# Schematic.net
KiCad netlist of a schematic drawn in Altium Designer
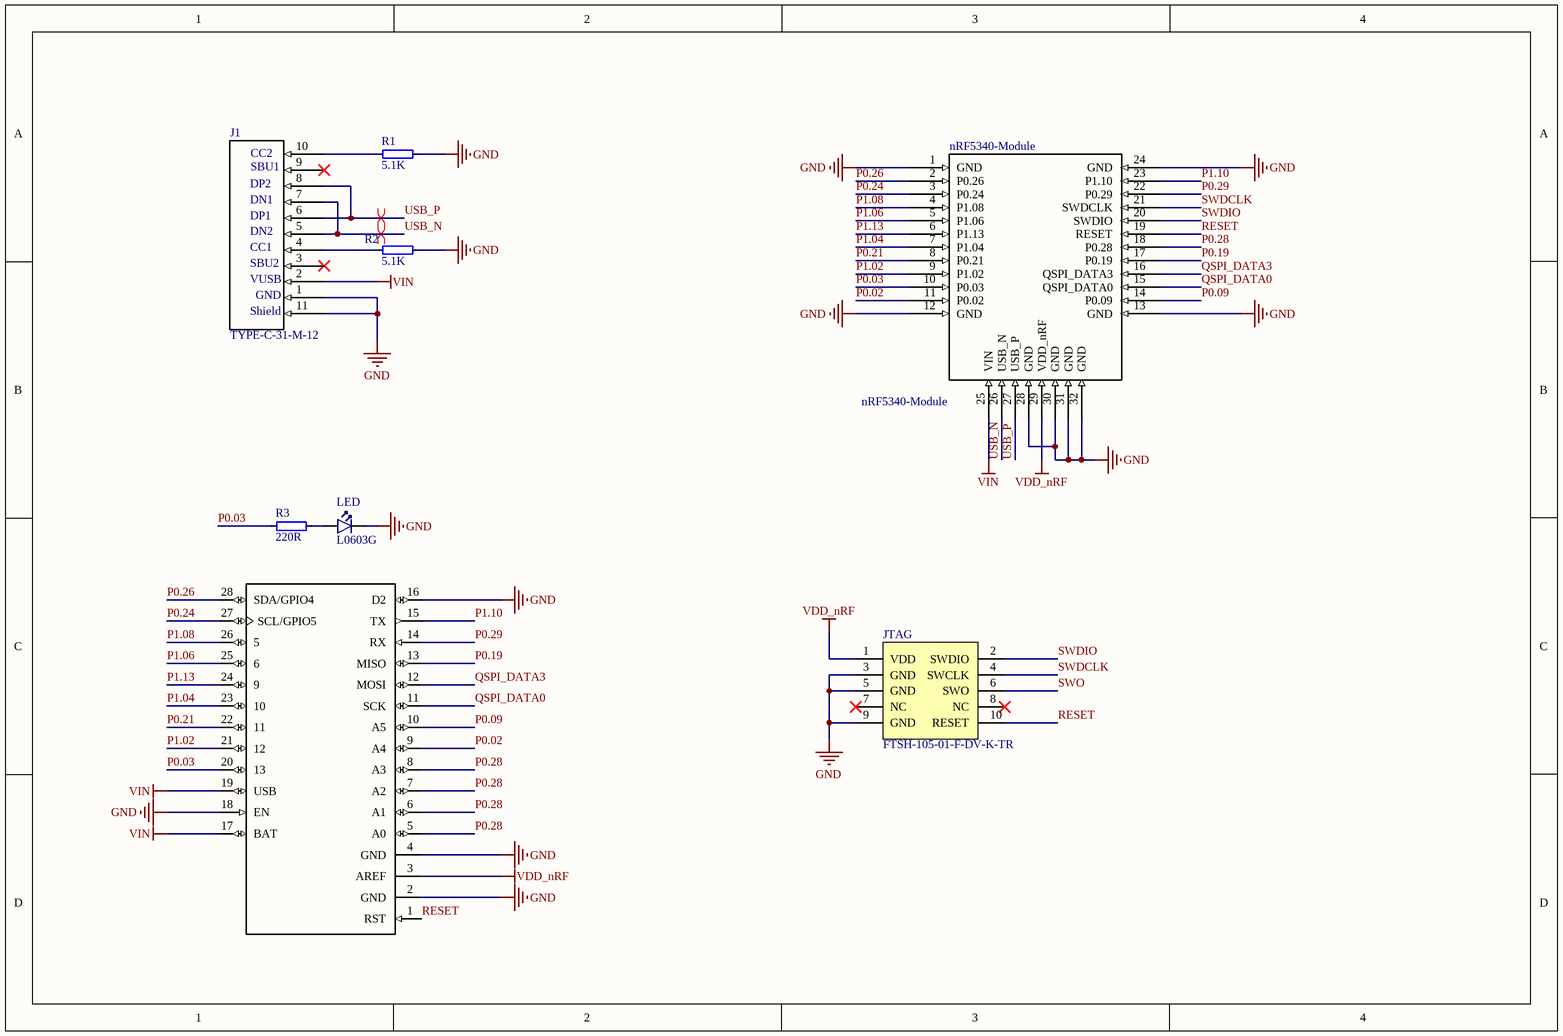
[diagram p0: Schematic.SchDoc]

(export (version "E")
  (design (tool "Eeschema 10.0.6"))
  (components
    (comp (ref "Feather")
      (value "DNP")
      (footprint "Feather")
      (description "Adafruit Feather Footprint")
      (fields (field (name "MF") "Adafruit Industries") (field (name "MP") "2821"))
      (libsource (lib "MISC") (part "Adafruit Feather"))
    )
    (comp (ref "J1")
      (value "TYPE-C-31-M-12")
      (footprint "TYPE-C-31-M-12")
      (description "USB C connector")
      (libsource (lib "Connector") (part "USB-C 2.0"))
    )
    (comp (ref "JTAG")
      (value "FTSH-105-01-F-DV-K-TR")
      (footprint "HDR_2x5-SMD-1.27mm-K_2")
      (description "Pin Header 2x5, 1.27mm (50mil), SMD, Keying Shroud")
      (fields
        (field (name "PART NUMBER") "Pin Header 2x5 SMD, 1.27mm, KS")
        (field (name "MANUFACTURER") "W-CON")
        (field (name "PUBLISHER") "Nordic Semiconductor")
      )
      (libsource (lib "Connector") (part "JTAG"))
    )
    (comp (ref "LED")
      (value "L0603G")
      (footprint "LED_0603")
      (description "LED, Green, 0603, 570nm, Vf=1.7V, 2.24..5.6mcd, - 40 to +100°C")
      (fields
        (field (name "PART NUMBER") "LG L29K Smartled Green")
        (field (name "MANUFACTURER") "Osram")
        (field (name "PUBLISHER") "Nordic Semiconductor")
      )
      (libsource (lib "Passives") (part "D{colon}LED"))
    )
    (comp (ref "nRF5340-Module")
      (value "nRF5340-Module")
      (footprint "nRF53-Module")
      (description "nRF5340-Module Available on https://www.hackster.io/kattemjau")
      (libsource (lib "MCU") (part "nRF5340-Module"))
    )
    (comp (ref "R1")
      (value "5.1K")
      (footprint "RES0603R")
      (description "Resistor, ±5%, 0.05W")
      (fields (field (name "PART NUMBER") "R0201-0R") (field (name "PUBLISHER") "Nordic Semiconductor"))
      (libsource (lib "Passives") (part "RES"))
    )
    (comp (ref "R2")
      (value "5.1K")
      (footprint "RES0603R")
      (description "Resistor, ±5%, 0.05W")
      (fields (field (name "PART NUMBER") "R0201-0R") (field (name "PUBLISHER") "Nordic Semiconductor"))
      (libsource (lib "Passives") (part "RES"))
    )
    (comp (ref "R3")
      (value "220R")
      (footprint "RES0603R")
      (description "Resistor, ±5%, 0.05W")
      (fields (field (name "PART NUMBER") "R0201-0R") (field (name "PUBLISHER") "Nordic Semiconductor"))
      (libsource (lib "Passives") (part "RES"))
    )
  )
  (nets
    (net (code "1") (name "/P0.02") (class "Default")
      (node (ref "Feather") (pin "9") (pinfunction "A4_9") (pintype "bidirectional"))
      (node (ref "nRF5340-Module") (pin "11") (pinfunction "P0.02_11") (pintype "input"))
    )
    (net (code "2") (name "/P0.03") (class "Default")
      (node (ref "Feather") (pin "20") (pinfunction "13_20") (pintype "bidirectional"))
      (node (ref "R3") (pin "1") (pinfunction "1_1") (pintype "passive"))
      (node (ref "nRF5340-Module") (pin "10") (pinfunction "P0.03_10") (pintype "input"))
    )
    (net (code "3") (name "/P0.09") (class "Default")
      (node (ref "Feather") (pin "10") (pinfunction "A5_10") (pintype "bidirectional"))
      (node (ref "nRF5340-Module") (pin "14") (pinfunction "P0.09_14") (pintype "input"))
    )
    (net (code "4") (name "/P0.19") (class "Default")
      (node (ref "Feather") (pin "13") (pinfunction "MISO_13") (pintype "bidirectional"))
      (node (ref "nRF5340-Module") (pin "17") (pinfunction "P0.19_17") (pintype "input"))
    )
    (net (code "5") (name "/P0.21") (class "Default")
      (node (ref "Feather") (pin "22") (pinfunction "11_22") (pintype "bidirectional"))
      (node (ref "nRF5340-Module") (pin "8") (pinfunction "P0.21_8") (pintype "input"))
    )
    (net (code "6") (name "/P0.24") (class "Default")
      (node (ref "Feather") (pin "27") (pinfunction "SCL/GPIO5_27") (pintype "bidirectional"))
      (node (ref "nRF5340-Module") (pin "3") (pinfunction "P0.24_3") (pintype "input"))
    )
    (net (code "7") (name "/P0.26") (class "Default")
      (node (ref "Feather") (pin "28") (pinfunction "SDA/GPIO4_28") (pintype "bidirectional"))
      (node (ref "nRF5340-Module") (pin "2") (pinfunction "P0.26_2") (pintype "input"))
    )
    (net (code "8") (name "/P0.28") (class "Default")
      (node (ref "Feather") (pin "5") (pinfunction "A0_5") (pintype "bidirectional"))
      (node (ref "Feather") (pin "6") (pinfunction "A1_6") (pintype "bidirectional"))
      (node (ref "Feather") (pin "7") (pinfunction "A2_7") (pintype "bidirectional"))
      (node (ref "Feather") (pin "8") (pinfunction "A3_8") (pintype "bidirectional"))
      (node (ref "nRF5340-Module") (pin "18") (pinfunction "P0.28_18") (pintype "input"))
    )
    (net (code "9") (name "/P0.29") (class "Default")
      (node (ref "Feather") (pin "14") (pinfunction "RX_14") (pintype "input"))
      (node (ref "nRF5340-Module") (pin "22") (pinfunction "P0.29_22") (pintype "input"))
    )
    (net (code "10") (name "/P1.02") (class "Default")
      (node (ref "Feather") (pin "21") (pinfunction "12_21") (pintype "bidirectional"))
      (node (ref "nRF5340-Module") (pin "9") (pinfunction "P1.02_9") (pintype "input"))
    )
    (net (code "11") (name "/P1.04") (class "Default")
      (node (ref "Feather") (pin "23") (pinfunction "10_23") (pintype "bidirectional"))
      (node (ref "nRF5340-Module") (pin "7") (pinfunction "P1.04_7") (pintype "input"))
    )
    (net (code "12") (name "/P1.06") (class "Default")
      (node (ref "Feather") (pin "25") (pinfunction "6_25") (pintype "bidirectional"))
      (node (ref "nRF5340-Module") (pin "5") (pinfunction "P1.06_5") (pintype "input"))
    )
    (net (code "13") (name "/P1.08") (class "Default")
      (node (ref "Feather") (pin "26") (pinfunction "5_26") (pintype "bidirectional"))
      (node (ref "nRF5340-Module") (pin "4") (pinfunction "P1.08_4") (pintype "input"))
    )
    (net (code "14") (name "/P1.10") (class "Default")
      (node (ref "Feather") (pin "15") (pinfunction "TX_15") (pintype "output"))
      (node (ref "nRF5340-Module") (pin "23") (pinfunction "P1.10_23") (pintype "input"))
    )
    (net (code "15") (name "/P1.13") (class "Default")
      (node (ref "Feather") (pin "24") (pinfunction "9_24") (pintype "bidirectional"))
      (node (ref "nRF5340-Module") (pin "6") (pinfunction "P1.13_6") (pintype "input"))
    )
    (net (code "16") (name "/QSPI_DATA0") (class "Default")
      (node (ref "Feather") (pin "11") (pinfunction "SCK_11") (pintype "bidirectional"))
      (node (ref "nRF5340-Module") (pin "15") (pinfunction "QSPI_DATA0_15") (pintype "input"))
    )
    (net (code "17") (name "/QSPI_DATA3") (class "Default")
      (node (ref "Feather") (pin "12") (pinfunction "MOSI_12") (pintype "bidirectional"))
      (node (ref "nRF5340-Module") (pin "16") (pinfunction "QSPI_DATA3_16") (pintype "input"))
    )
    (net (code "18") (name "/RESET") (class "Default")
      (node (ref "Feather") (pin "1") (pinfunction "RST_1") (pintype "input"))
      (node (ref "JTAG") (pin "10") (pinfunction "RESET_10") (pintype "passive"))
      (node (ref "nRF5340-Module") (pin "19") (pinfunction "RESET_19") (pintype "input"))
    )
    (net (code "19") (name "/SWDCLK") (class "Default")
      (node (ref "JTAG") (pin "4") (pinfunction "SWCLK_4") (pintype "passive"))
      (node (ref "nRF5340-Module") (pin "21") (pinfunction "SWDCLK_21") (pintype "input"))
    )
    (net (code "20") (name "/SWDIO") (class "Default")
      (node (ref "JTAG") (pin "2") (pinfunction "SWDIO_2") (pintype "passive"))
      (node (ref "nRF5340-Module") (pin "20") (pinfunction "SWDIO_20") (pintype "input"))
    )
    (net (code "21") (name "/SWO") (class "Default")
      (node (ref "JTAG") (pin "6") (pinfunction "SWO_6") (pintype "passive"))
    )
    (net (code "22") (name "/USB_N") (class "Default")
      (node (ref "J1") (pin "5") (pintype "input"))
      (node (ref "J1") (pin "7") (pintype "input"))
      (node (ref "nRF5340-Module") (pin "26") (pinfunction "USB_N_26") (pintype "input"))
    )
    (net (code "23") (name "/USB_P") (class "Default")
      (node (ref "J1") (pin "6") (pintype "input"))
      (node (ref "J1") (pin "8") (pintype "input"))
      (node (ref "nRF5340-Module") (pin "27") (pinfunction "USB_P_27") (pintype "input"))
    )
    (net (code "24") (name "GND") (class "Default")
      (node (ref "Feather") (pin "16") (pinfunction "D2_16") (pintype "bidirectional"))
      (node (ref "Feather") (pin "18") (pinfunction "EN_18") (pintype "input"))
      (node (ref "Feather") (pin "2") (pinfunction "GND_2") (pintype "power_in"))
      (node (ref "Feather") (pin "4") (pinfunction "GND_4") (pintype "power_in"))
      (node (ref "J1") (pin "1") (pintype "input"))
      (node (ref "J1") (pin "11") (pintype "input"))
      (node (ref "JTAG") (pin "3") (pinfunction "GND_3") (pintype "passive"))
      (node (ref "JTAG") (pin "5") (pinfunction "GND_5") (pintype "passive"))
      (node (ref "JTAG") (pin "9") (pinfunction "GND_9") (pintype "passive"))
      (node (ref "LED") (pin "1") (pinfunction "C_1") (pintype "passive"))
      (node (ref "R1") (pin "2") (pinfunction "2_2") (pintype "passive"))
      (node (ref "R2") (pin "2") (pinfunction "2_2") (pintype "passive"))
      (node (ref "nRF5340-Module") (pin "1") (pinfunction "GND_1") (pintype "input"))
      (node (ref "nRF5340-Module") (pin "12") (pinfunction "GND_12") (pintype "input"))
      (node (ref "nRF5340-Module") (pin "13") (pinfunction "GND_13") (pintype "input"))
      (node (ref "nRF5340-Module") (pin "24") (pinfunction "GND_24") (pintype "input"))
      (node (ref "nRF5340-Module") (pin "28") (pinfunction "GND_28") (pintype "input"))
      (node (ref "nRF5340-Module") (pin "30") (pinfunction "GND_30") (pintype "input"))
      (node (ref "nRF5340-Module") (pin "31") (pinfunction "GND_31") (pintype "input"))
      (node (ref "nRF5340-Module") (pin "32") (pinfunction "GND_32") (pintype "input"))
    )
    (net (code "25") (name "Net-(J1-Pad4)") (class "Default")
      (node (ref "J1") (pin "4") (pintype "input"))
      (node (ref "R2") (pin "1") (pinfunction "1_1") (pintype "passive"))
    )
    (net (code "26") (name "Net-(J1-Pad10)") (class "Default")
      (node (ref "J1") (pin "10") (pintype "input"))
      (node (ref "R1") (pin "1") (pinfunction "1_1") (pintype "passive"))
    )
    (net (code "27") (name "Net-(LED-A)") (class "Default")
      (node (ref "LED") (pin "2") (pinfunction "A_2") (pintype "passive"))
      (node (ref "R3") (pin "2") (pinfunction "2_2") (pintype "passive"))
    )
    (net (code "28") (name "VDD_nRF") (class "Default")
      (node (ref "Feather") (pin "3") (pinfunction "AREF_3") (pintype "power_in"))
      (node (ref "JTAG") (pin "1") (pinfunction "VDD_1") (pintype "passive"))
      (node (ref "nRF5340-Module") (pin "29") (pinfunction "VDD_nRF_29") (pintype "input"))
    )
    (net (code "29") (name "VIN") (class "Default")
      (node (ref "Feather") (pin "17") (pinfunction "BAT_17") (pintype "bidirectional"))
      (node (ref "Feather") (pin "19") (pinfunction "USB_19") (pintype "bidirectional"))
      (node (ref "J1") (pin "2") (pintype "input"))
      (node (ref "nRF5340-Module") (pin "25") (pinfunction "VIN_25") (pintype "input"))
    )
    (net (code "30") (name "unconnected-(J1-Pad3)") (class "Default")
      (node (ref "J1") (pin "3") (pintype "input+no_connect"))
    )
    (net (code "31") (name "unconnected-(J1-Pad9)") (class "Default")
      (node (ref "J1") (pin "9") (pintype "input+no_connect"))
    )
    (net (code "32") (name "unconnected-(JTAG-NC-Pad7)") (class "Default")
      (node (ref "JTAG") (pin "7") (pinfunction "NC_7") (pintype "passive+no_connect"))
    )
    (net (code "33") (name "unconnected-(JTAG-NC-Pad8)") (class "Default")
      (node (ref "JTAG") (pin "8") (pinfunction "NC_8") (pintype "passive+no_connect"))
    )
  )
)
